# MIDI_Breakout.net
KiCad netlist of a schematic drawn in EAGLE
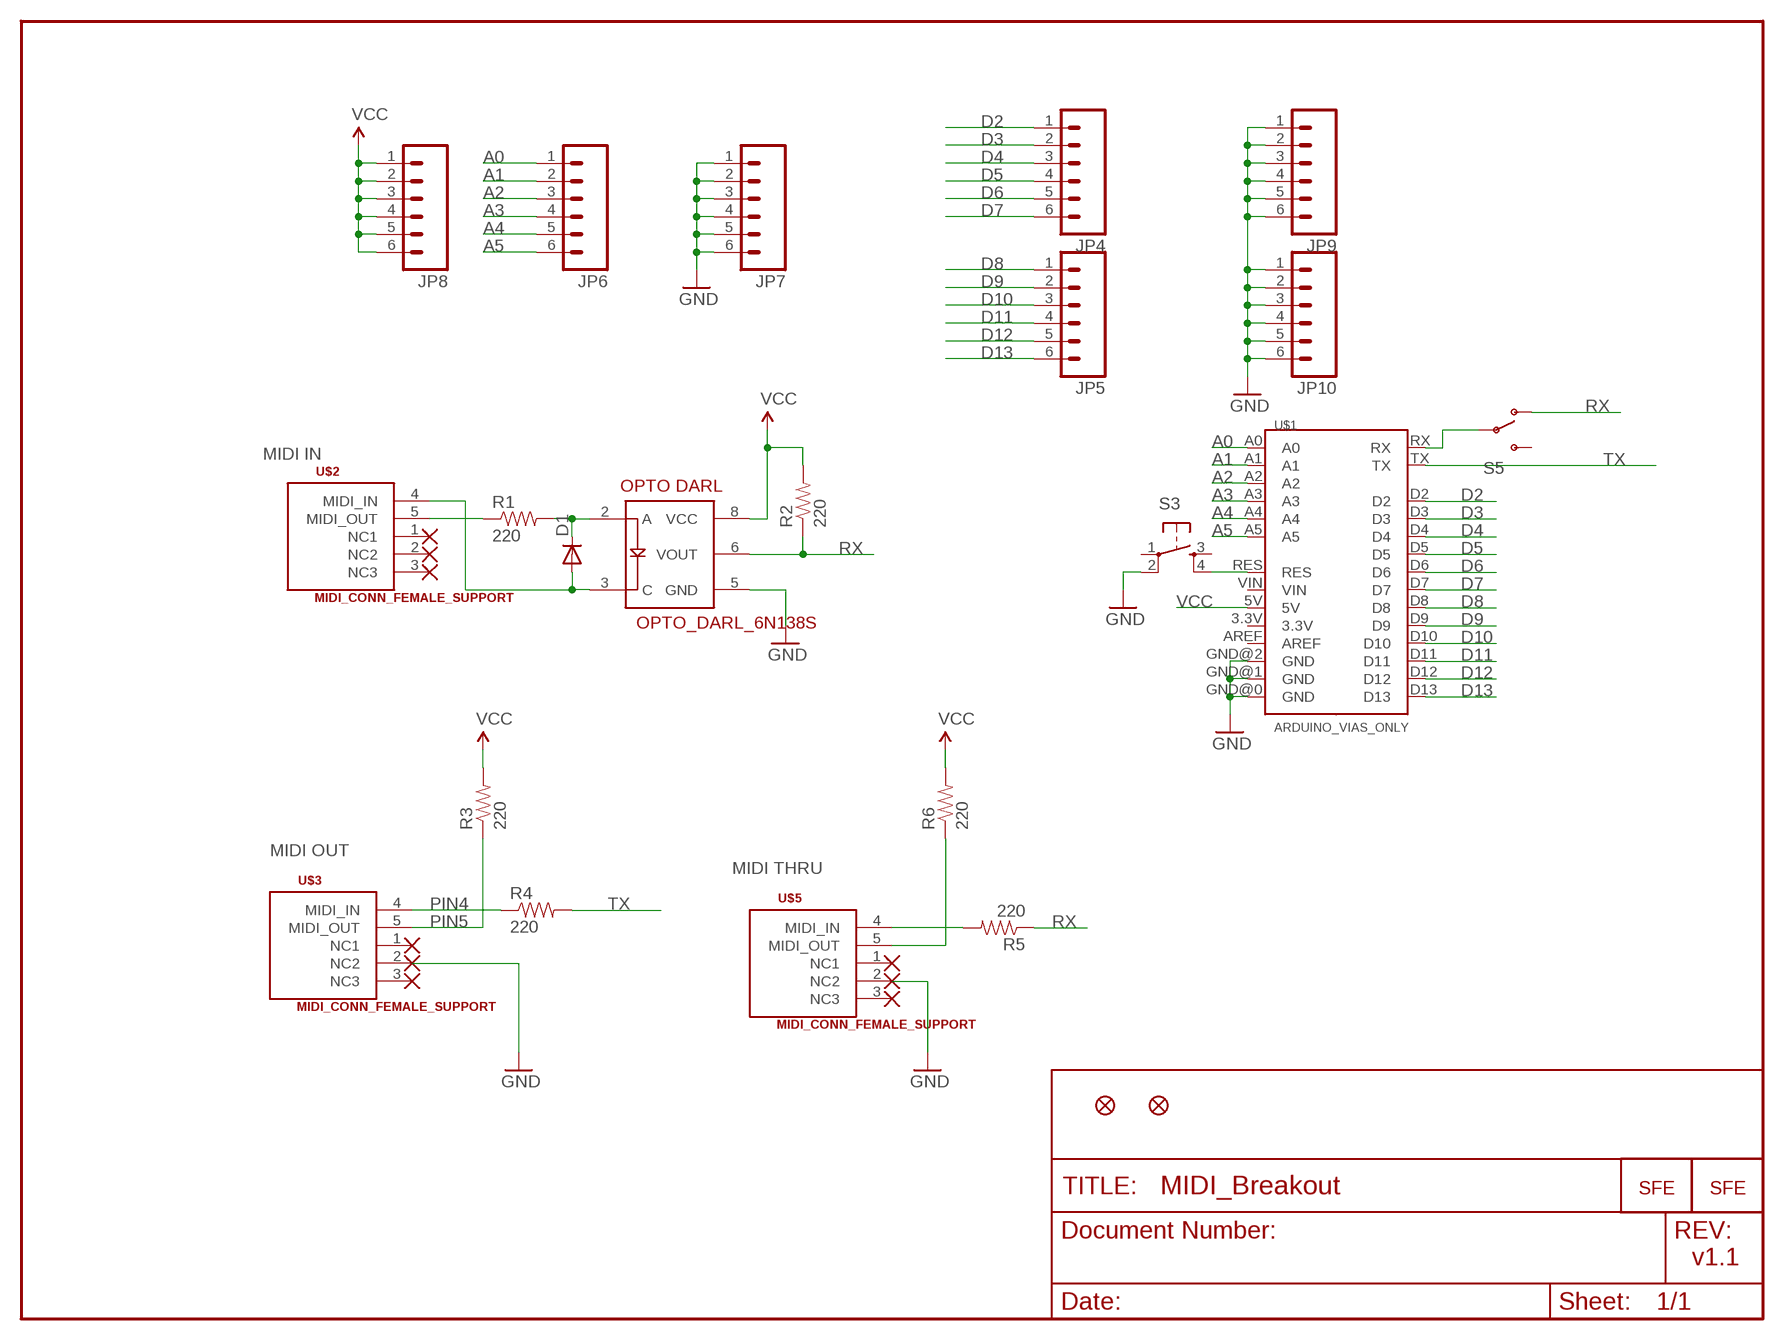
[diagram p0: schematic, sheet 1]

(export (version "E")
  (design (tool "Eeschema 10.0.6"))
  (components
    (comp (ref "D1")
      (value "DIODESMA")
      (footprint "eagle-import:SMA-DIODE")
      (libsource (lib "eagle-import") (part "DIODESMA"))
    )
    (comp (ref "JP1")
      (value "FIDUCIAL1X2")
      (footprint "eagle-import:FIDUCIAL-1X2")
      (libsource (lib "eagle-import") (part "FIDUCIAL1X2"))
    )
    (comp (ref "JP2")
      (value "FIDUCIAL1X2")
      (footprint "eagle-import:FIDUCIAL-1X2")
      (libsource (lib "eagle-import") (part "FIDUCIAL1X2"))
    )
    (comp (ref "JP3")
      (value "LOGO-SFENEW")
      (footprint "eagle-import:SFE-NEW-WEBLOGO")
      (libsource (lib "eagle-import") (part "LOGO-SFENEW"))
    )
    (comp (ref "JP4")
      (value "M06SIP")
      (footprint "eagle-import:1X06")
      (libsource (lib "eagle-import") (part "M06SIP"))
    )
    (comp (ref "JP5")
      (value "M06SIP")
      (footprint "eagle-import:1X06")
      (libsource (lib "eagle-import") (part "M06SIP"))
    )
    (comp (ref "JP6")
      (value "M06SIP")
      (footprint "eagle-import:1X06")
      (libsource (lib "eagle-import") (part "M06SIP"))
    )
    (comp (ref "JP7")
      (value "M06SIP")
      (footprint "eagle-import:1X06")
      (libsource (lib "eagle-import") (part "M06SIP"))
    )
    (comp (ref "JP8")
      (value "M06SIP")
      (footprint "eagle-import:1X06")
      (libsource (lib "eagle-import") (part "M06SIP"))
    )
    (comp (ref "JP9")
      (value "M06SIP")
      (footprint "eagle-import:1X06")
      (libsource (lib "eagle-import") (part "M06SIP"))
    )
    (comp (ref "JP10")
      (value "M06SIP")
      (footprint "eagle-import:1X06")
      (libsource (lib "eagle-import") (part "M06SIP"))
    )
    (comp (ref "JP11")
      (value "LOGO-SFENEW")
      (footprint "eagle-import:SFE-NEW-WEBLOGO")
      (libsource (lib "eagle-import") (part "LOGO-SFENEW"))
    )
    (comp (ref "R1")
      (value "220")
      (footprint "eagle-import:0402-RES")
      (libsource (lib "eagle-import") (part "RESISTOR0402-RES"))
    )
    (comp (ref "R2")
      (value "220")
      (footprint "eagle-import:0402-RES")
      (libsource (lib "eagle-import") (part "RESISTOR0402-RES"))
    )
    (comp (ref "R3")
      (value "220")
      (footprint "eagle-import:0402-RES")
      (libsource (lib "eagle-import") (part "RESISTOR0402-RES"))
    )
    (comp (ref "R4")
      (value "220")
      (footprint "eagle-import:0402-RES")
      (libsource (lib "eagle-import") (part "RESISTOR0402-RES"))
    )
    (comp (ref "R5")
      (value "220")
      (footprint "eagle-import:0402-RES")
      (libsource (lib "eagle-import") (part "RESISTOR0402-RES"))
    )
    (comp (ref "R6")
      (value "220")
      (footprint "eagle-import:0402-RES")
      (libsource (lib "eagle-import") (part "RESISTOR0402-RES"))
    )
    (comp (ref "S3")
      (value "TAC_SWITCHSMD")
      (footprint "eagle-import:TACTILE_SWITCH_SMD")
      (libsource (lib "eagle-import") (part "TAC_SWITCHSMD"))
    )
    (comp (ref "S5")
      (value "SWITCH-SPSTSMD")
      (footprint "eagle-import:AYZ0202")
      (libsource (lib "eagle-import") (part "SWITCH-SPSTSMD"))
    )
    (comp (ref "U$1")
      (value "ARDUINO_VIAS_ONLY")
      (footprint "eagle-import:DUEMILANOVE_VIAS")
      (libsource (lib "eagle-import") (part "ARDUINO_VIAS_ONLY"))
    )
    (comp (ref "U$2")
      (value "MIDI_CONN_FEMALE_SUPPORT")
      (footprint "eagle-import:DIN_5_FEMALE_SUPPORT")
      (libsource (lib "eagle-import") (part "MIDI_CONN_FEMALE_SUPPORT"))
    )
    (comp (ref "U$3")
      (value "MIDI_CONN_FEMALE_SUPPORT")
      (footprint "eagle-import:DIN_5_FEMALE_SUPPORT")
      (libsource (lib "eagle-import") (part "MIDI_CONN_FEMALE_SUPPORT"))
    )
    (comp (ref "U$5")
      (value "MIDI_CONN_FEMALE_SUPPORT")
      (footprint "eagle-import:DIN_5_FEMALE_SUPPORT")
      (libsource (lib "eagle-import") (part "MIDI_CONN_FEMALE_SUPPORT"))
    )
    (comp (ref "U$6")
      (value "OPTO_DARL_6N138S")
      (footprint "eagle-import:8-SMD")
      (libsource (lib "eagle-import") (part "OPTO_DARL_6N138S"))
    )
  )
  (nets
    (net (code "1") (name "/A0") (class "Default")
      (node (ref "JP6") (pin "1") (pinfunction "1_1") (pintype "passive"))
      (node (ref "U$1") (pin "A0") (pinfunction "A0_A0") (pintype "bidirectional"))
    )
    (net (code "2") (name "/A1") (class "Default")
      (node (ref "JP6") (pin "2") (pinfunction "2_2") (pintype "passive"))
      (node (ref "U$1") (pin "A1") (pinfunction "A1_A1") (pintype "bidirectional"))
    )
    (net (code "3") (name "/A2") (class "Default")
      (node (ref "JP6") (pin "3") (pinfunction "3_3") (pintype "passive"))
      (node (ref "U$1") (pin "A2") (pinfunction "A2_A2") (pintype "bidirectional"))
    )
    (net (code "4") (name "/A3") (class "Default")
      (node (ref "JP6") (pin "4") (pinfunction "4_4") (pintype "passive"))
      (node (ref "U$1") (pin "A3") (pinfunction "A3_A3") (pintype "bidirectional"))
    )
    (net (code "5") (name "/A4") (class "Default")
      (node (ref "JP6") (pin "5") (pinfunction "5_5") (pintype "passive"))
      (node (ref "U$1") (pin "A4") (pinfunction "A4_A4") (pintype "bidirectional"))
    )
    (net (code "6") (name "/A5") (class "Default")
      (node (ref "JP6") (pin "6") (pinfunction "6_6") (pintype "passive"))
      (node (ref "U$1") (pin "A5") (pinfunction "A5_A5") (pintype "bidirectional"))
    )
    (net (code "7") (name "/D2") (class "Default")
      (node (ref "JP4") (pin "1") (pinfunction "1_1") (pintype "passive"))
      (node (ref "U$1") (pin "D2") (pinfunction "D2_D2") (pintype "bidirectional"))
    )
    (net (code "8") (name "/D3") (class "Default")
      (node (ref "JP4") (pin "2") (pinfunction "2_2") (pintype "passive"))
      (node (ref "U$1") (pin "D3") (pinfunction "D3_D3") (pintype "bidirectional"))
    )
    (net (code "9") (name "/D4") (class "Default")
      (node (ref "JP4") (pin "3") (pinfunction "3_3") (pintype "passive"))
      (node (ref "U$1") (pin "D4") (pinfunction "D4_D4") (pintype "bidirectional"))
    )
    (net (code "10") (name "/D5") (class "Default")
      (node (ref "JP4") (pin "4") (pinfunction "4_4") (pintype "passive"))
      (node (ref "U$1") (pin "D5") (pinfunction "D5_D5") (pintype "bidirectional"))
    )
    (net (code "11") (name "/D6") (class "Default")
      (node (ref "JP4") (pin "5") (pinfunction "5_5") (pintype "passive"))
      (node (ref "U$1") (pin "D6") (pinfunction "D6_D6") (pintype "bidirectional"))
    )
    (net (code "12") (name "/D7") (class "Default")
      (node (ref "JP4") (pin "6") (pinfunction "6_6") (pintype "passive"))
      (node (ref "U$1") (pin "D7") (pinfunction "D7_D7") (pintype "bidirectional"))
    )
    (net (code "13") (name "/D8") (class "Default")
      (node (ref "JP5") (pin "1") (pinfunction "1_1") (pintype "passive"))
      (node (ref "U$1") (pin "D8") (pinfunction "D8_D8") (pintype "bidirectional"))
    )
    (net (code "14") (name "/D9") (class "Default")
      (node (ref "JP5") (pin "2") (pinfunction "2_2") (pintype "passive"))
      (node (ref "U$1") (pin "D9") (pinfunction "D9_D9") (pintype "bidirectional"))
    )
    (net (code "15") (name "/D10") (class "Default")
      (node (ref "JP5") (pin "3") (pinfunction "3_3") (pintype "passive"))
      (node (ref "U$1") (pin "D10") (pinfunction "D10_D10") (pintype "bidirectional"))
    )
    (net (code "16") (name "/D11") (class "Default")
      (node (ref "JP5") (pin "4") (pinfunction "4_4") (pintype "passive"))
      (node (ref "U$1") (pin "D11") (pinfunction "D11_D11") (pintype "bidirectional"))
    )
    (net (code "17") (name "/D12") (class "Default")
      (node (ref "JP5") (pin "5") (pinfunction "5_5") (pintype "passive"))
      (node (ref "U$1") (pin "D12") (pinfunction "D12_D12") (pintype "bidirectional"))
    )
    (net (code "18") (name "/D13") (class "Default")
      (node (ref "JP5") (pin "6") (pinfunction "6_6") (pintype "passive"))
      (node (ref "U$1") (pin "D13") (pinfunction "D13_D13") (pintype "bidirectional"))
    )
    (net (code "19") (name "/RX") (class "Default")
      (node (ref "R2") (pin "1") (pinfunction "1_1") (pintype "passive"))
      (node (ref "R5") (pin "1") (pinfunction "1_1") (pintype "passive"))
      (node (ref "S5") (pin "1") (pinfunction "O_1") (pintype "passive"))
      (node (ref "U$6") (pin "6") (pinfunction "VOUT_6") (pintype "bidirectional"))
    )
    (net (code "20") (name "/TX") (class "Default")
      (node (ref "R4") (pin "2") (pinfunction "2_2") (pintype "passive"))
      (node (ref "U$1") (pin "TX") (pinfunction "TX_TX") (pintype "bidirectional"))
    )
    (net (code "21") (name "GND") (class "Default")
      (node (ref "JP10") (pin "1") (pinfunction "1_1") (pintype "passive"))
      (node (ref "JP10") (pin "2") (pinfunction "2_2") (pintype "passive"))
      (node (ref "JP10") (pin "3") (pinfunction "3_3") (pintype "passive"))
      (node (ref "JP10") (pin "4") (pinfunction "4_4") (pintype "passive"))
      (node (ref "JP10") (pin "5") (pinfunction "5_5") (pintype "passive"))
      (node (ref "JP10") (pin "6") (pinfunction "6_6") (pintype "passive"))
      (node (ref "JP7") (pin "1") (pinfunction "1_1") (pintype "passive"))
      (node (ref "JP7") (pin "2") (pinfunction "2_2") (pintype "passive"))
      (node (ref "JP7") (pin "3") (pinfunction "3_3") (pintype "passive"))
      (node (ref "JP7") (pin "4") (pinfunction "4_4") (pintype "passive"))
      (node (ref "JP7") (pin "5") (pinfunction "5_5") (pintype "passive"))
      (node (ref "JP7") (pin "6") (pinfunction "6_6") (pintype "passive"))
      (node (ref "JP9") (pin "1") (pinfunction "1_1") (pintype "passive"))
      (node (ref "JP9") (pin "2") (pinfunction "2_2") (pintype "passive"))
      (node (ref "JP9") (pin "3") (pinfunction "3_3") (pintype "passive"))
      (node (ref "JP9") (pin "4") (pinfunction "4_4") (pintype "passive"))
      (node (ref "JP9") (pin "5") (pinfunction "5_5") (pintype "passive"))
      (node (ref "JP9") (pin "6") (pinfunction "6_6") (pintype "passive"))
      (node (ref "S3") (pin "2") (pinfunction "2_2") (pintype "passive"))
      (node (ref "U$1") (pin "GND@0") (pinfunction "GND_GND@0") (pintype "bidirectional"))
      (node (ref "U$1") (pin "GND@1") (pinfunction "GND_GND@1") (pintype "bidirectional"))
      (node (ref "U$1") (pin "GND@2") (pinfunction "GND_GND@2") (pintype "bidirectional"))
      (node (ref "U$3") (pin "2") (pinfunction "NC2_2") (pintype "bidirectional"))
      (node (ref "U$5") (pin "2") (pinfunction "NC2_2") (pintype "bidirectional"))
      (node (ref "U$6") (pin "5") (pinfunction "GND_5") (pintype "bidirectional"))
    )
    (net (code "22") (name "Net-(S3-Pad4)") (class "Default")
      (node (ref "S3") (pin "4") (pinfunction "4_4") (pintype "passive"))
      (node (ref "U$1") (pin "RES") (pinfunction "RES_RES") (pintype "bidirectional"))
    )
    (net (code "23") (name "Net-(S5-P)") (class "Default")
      (node (ref "S5") (pin "2") (pinfunction "P_2") (pintype "passive"))
      (node (ref "U$1") (pin "RX") (pinfunction "RX_RX") (pintype "bidirectional"))
    )
    (net (code "24") (name "Net-(U$2-MIDI_IN)") (class "Default")
      (node (ref "D1") (pin "A") (pinfunction "A_A") (pintype "passive"))
      (node (ref "U$2") (pin "4") (pinfunction "MIDI_IN_4") (pintype "bidirectional"))
      (node (ref "U$6") (pin "3") (pinfunction "C_3") (pintype "bidirectional"))
    )
    (net (code "25") (name "Net-(U$2-MIDI_OUT)") (class "Default")
      (node (ref "R1") (pin "1") (pinfunction "1_1") (pintype "passive"))
      (node (ref "U$2") (pin "5") (pinfunction "MIDI_OUT_5") (pintype "bidirectional"))
    )
    (net (code "26") (name "Net-(U$3-MIDI_IN)") (class "Default")
      (node (ref "R4") (pin "1") (pinfunction "1_1") (pintype "passive"))
      (node (ref "U$3") (pin "4") (pinfunction "MIDI_IN_4") (pintype "bidirectional"))
    )
    (net (code "27") (name "Net-(U$3-MIDI_OUT)") (class "Default")
      (node (ref "R3") (pin "1") (pinfunction "1_1") (pintype "passive"))
      (node (ref "U$3") (pin "5") (pinfunction "MIDI_OUT_5") (pintype "bidirectional"))
    )
    (net (code "28") (name "Net-(U$5-MIDI_IN)") (class "Default")
      (node (ref "R5") (pin "2") (pinfunction "2_2") (pintype "passive"))
      (node (ref "U$5") (pin "4") (pinfunction "MIDI_IN_4") (pintype "bidirectional"))
    )
    (net (code "29") (name "Net-(U$5-MIDI_OUT)") (class "Default")
      (node (ref "R6") (pin "1") (pinfunction "1_1") (pintype "passive"))
      (node (ref "U$5") (pin "5") (pinfunction "MIDI_OUT_5") (pintype "bidirectional"))
    )
    (net (code "30") (name "Net-(U$6-A)") (class "Default")
      (node (ref "D1") (pin "C") (pinfunction "C_C") (pintype "passive"))
      (node (ref "R1") (pin "2") (pinfunction "2_2") (pintype "passive"))
      (node (ref "U$6") (pin "2") (pinfunction "A_2") (pintype "bidirectional"))
    )
    (net (code "31") (name "VCC") (class "Default")
      (node (ref "JP8") (pin "1") (pinfunction "1_1") (pintype "passive"))
      (node (ref "JP8") (pin "2") (pinfunction "2_2") (pintype "passive"))
      (node (ref "JP8") (pin "3") (pinfunction "3_3") (pintype "passive"))
      (node (ref "JP8") (pin "4") (pinfunction "4_4") (pintype "passive"))
      (node (ref "JP8") (pin "5") (pinfunction "5_5") (pintype "passive"))
      (node (ref "JP8") (pin "6") (pinfunction "6_6") (pintype "passive"))
      (node (ref "R2") (pin "2") (pinfunction "2_2") (pintype "passive"))
      (node (ref "R3") (pin "2") (pinfunction "2_2") (pintype "passive"))
      (node (ref "R6") (pin "2") (pinfunction "2_2") (pintype "passive"))
      (node (ref "U$1") (pin "5V") (pinfunction "5V_5V") (pintype "bidirectional"))
      (node (ref "U$6") (pin "8") (pinfunction "VCC_8") (pintype "bidirectional"))
    )
    (net (code "32") (name "unconnected-(S3-Pad1)") (class "Default")
      (node (ref "S3") (pin "1") (pinfunction "1_1") (pintype "passive"))
    )
    (net (code "33") (name "unconnected-(S3-Pad3)") (class "Default")
      (node (ref "S3") (pin "3") (pinfunction "3_3") (pintype "passive"))
    )
    (net (code "34") (name "unconnected-(S5-S-Pad3)") (class "Default")
      (node (ref "S5") (pin "3") (pinfunction "S_3") (pintype "passive"))
    )
    (net (code "35") (name "unconnected-(U$1-Pad3.3V)") (class "Default")
      (node (ref "U$1") (pin "3.3V") (pinfunction "3.3V_3.3V") (pintype "bidirectional"))
    )
    (net (code "36") (name "unconnected-(U$1-PadAREF)") (class "Default")
      (node (ref "U$1") (pin "AREF") (pinfunction "AREF_AREF") (pintype "bidirectional"))
    )
    (net (code "37") (name "unconnected-(U$1-PadVIN)") (class "Default")
      (node (ref "U$1") (pin "VIN") (pinfunction "VIN_VIN") (pintype "bidirectional"))
    )
    (net (code "38") (name "unconnected-(U$2-NC1-Pad1)") (class "Default")
      (node (ref "U$2") (pin "1") (pinfunction "NC1_1") (pintype "bidirectional"))
    )
    (net (code "39") (name "unconnected-(U$2-NC2-Pad2)") (class "Default")
      (node (ref "U$2") (pin "2") (pinfunction "NC2_2") (pintype "bidirectional"))
    )
    (net (code "40") (name "unconnected-(U$2-NC3-Pad3)") (class "Default")
      (node (ref "U$2") (pin "3") (pinfunction "NC3_3") (pintype "bidirectional"))
    )
    (net (code "41") (name "unconnected-(U$3-NC1-Pad1)") (class "Default")
      (node (ref "U$3") (pin "1") (pinfunction "NC1_1") (pintype "bidirectional"))
    )
    (net (code "42") (name "unconnected-(U$3-NC3-Pad3)") (class "Default")
      (node (ref "U$3") (pin "3") (pinfunction "NC3_3") (pintype "bidirectional"))
    )
    (net (code "43") (name "unconnected-(U$5-NC1-Pad1)") (class "Default")
      (node (ref "U$5") (pin "1") (pinfunction "NC1_1") (pintype "bidirectional"))
    )
    (net (code "44") (name "unconnected-(U$5-NC3-Pad3)") (class "Default")
      (node (ref "U$5") (pin "3") (pinfunction "NC3_3") (pintype "bidirectional"))
    )
  )
)
